# Central_march16.net
KiCad netlist of a schematic drawn in EAGLE
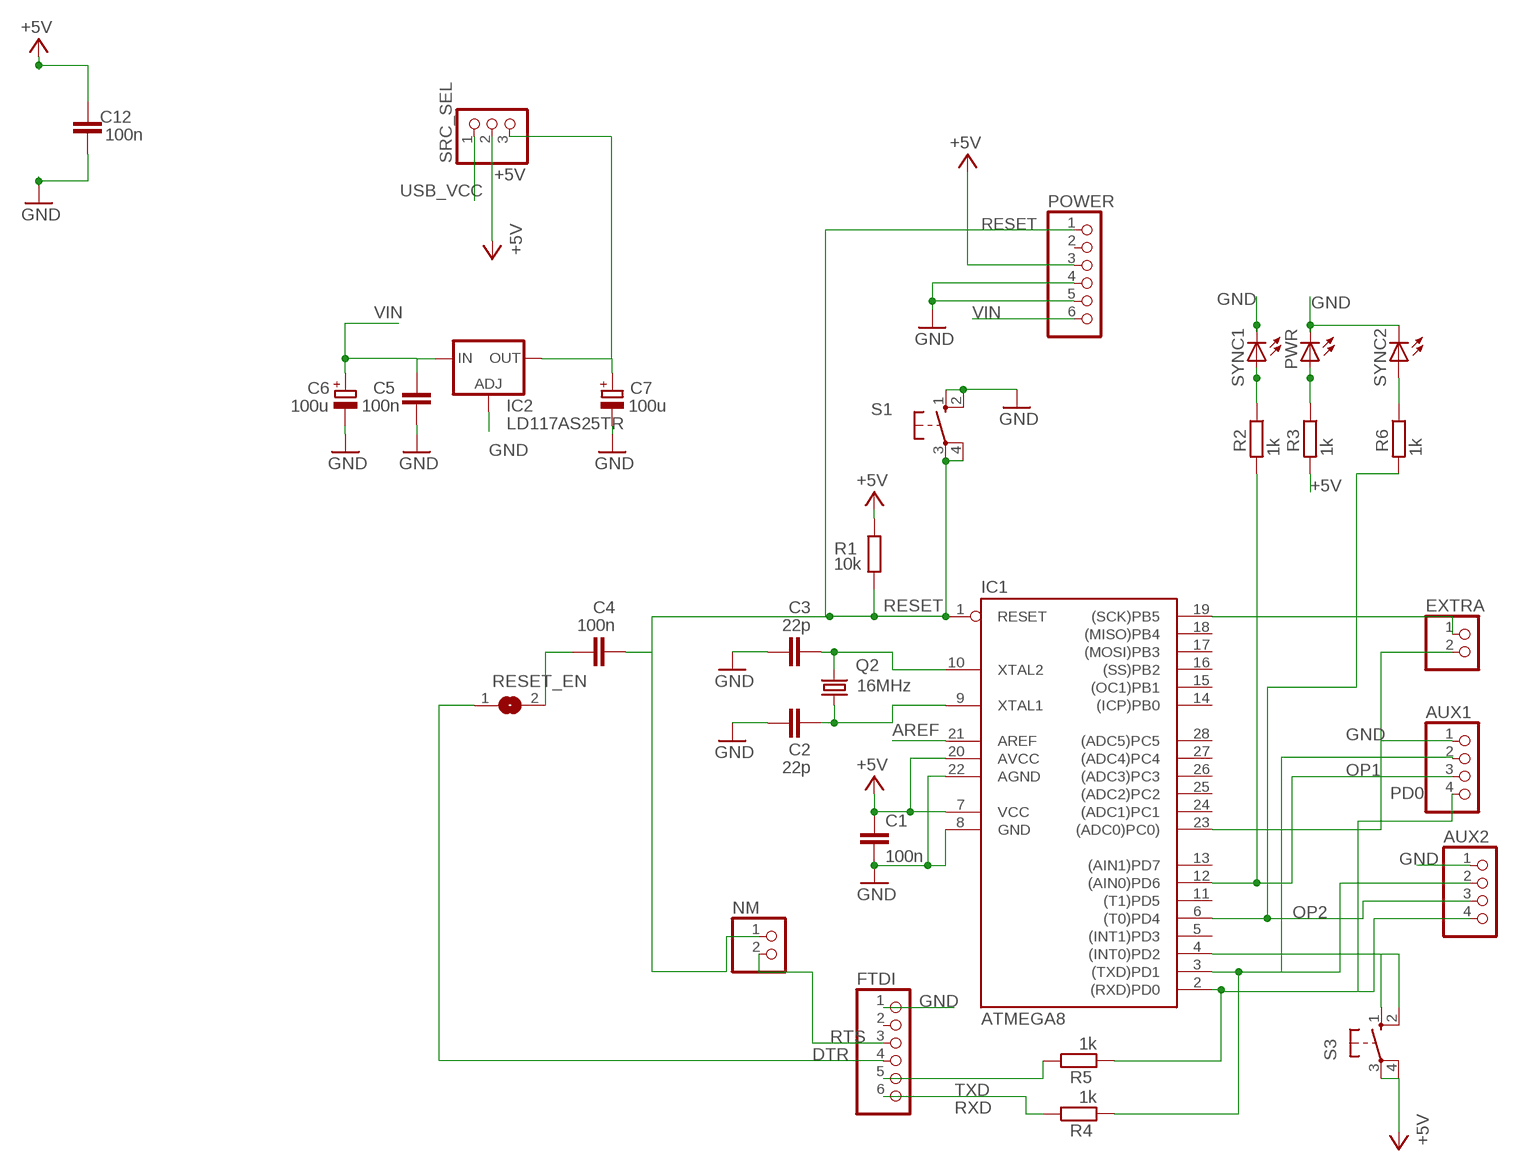
[diagram p0: schematic, sheet 1]

(export (version "E")
  (design (tool "Eeschema 10.0.6"))
  (components
    (comp (ref "AUX1")
      (value "PINHD-1X4")
      (footprint "eagle-import:1X04")
      (libsource (lib "eagle-import") (part "PINHD-1X4"))
    )
    (comp (ref "AUX2")
      (value "PINHD-1X4")
      (footprint "eagle-import:1X04")
      (libsource (lib "eagle-import") (part "PINHD-1X4"))
    )
    (comp (ref "C1")
      (value "100n")
      (footprint "eagle-import:C1206")
      (libsource (lib "eagle-import") (part "C-EUC1206"))
    )
    (comp (ref "C2")
      (value "22p")
      (footprint "eagle-import:C1206")
      (libsource (lib "eagle-import") (part "C-EUC1206"))
    )
    (comp (ref "C3")
      (value "22p")
      (footprint "eagle-import:C1206")
      (libsource (lib "eagle-import") (part "C-EUC1206"))
    )
    (comp (ref "C4")
      (value "100n")
      (footprint "eagle-import:C1206")
      (libsource (lib "eagle-import") (part "C-EUC1206"))
    )
    (comp (ref "C5")
      (value "100n")
      (footprint "eagle-import:C1206")
      (libsource (lib "eagle-import") (part "C-EUC1206"))
    )
    (comp (ref "C6")
      (value "100u")
      (footprint "eagle-import:PANASONIC_D")
      (libsource (lib "eagle-import") (part "CPOL-EUD"))
    )
    (comp (ref "C7")
      (value "100u")
      (footprint "eagle-import:PANASONIC_D")
      (libsource (lib "eagle-import") (part "CPOL-EUD"))
    )
    (comp (ref "C12")
      (value "100n")
      (footprint "eagle-import:C1206")
      (libsource (lib "eagle-import") (part "C-EUC1206"))
    )
    (comp (ref "EXTRA")
      (value "PINHD-1X2")
      (footprint "eagle-import:1X02")
      (libsource (lib "eagle-import") (part "PINHD-1X2"))
    )
    (comp (ref "FTDI")
      (value "PINHD-1X6")
      (footprint "eagle-import:1X06")
      (libsource (lib "eagle-import") (part "PINHD-1X6"))
    )
    (comp (ref "IC1")
      (value "ATMEGA8")
      (footprint "eagle-import:DIL28-3")
      (libsource (lib "eagle-import") (part "AT90S4433P"))
    )
    (comp (ref "IC2")
      (value "LD117AS25TR")
      (footprint "eagle-import:SOT223")
      (libsource (lib "eagle-import") (part "LD117A?S25TR"))
    )
    (comp (ref "NM")
      (value "PINHD-1X2")
      (footprint "eagle-import:1X02")
      (libsource (lib "eagle-import") (part "PINHD-1X2"))
    )
    (comp (ref "POWER")
      (value "PINHD-1X6")
      (footprint "eagle-import:1X06")
      (libsource (lib "eagle-import") (part "PINHD-1X6"))
    )
    (comp (ref "PWR")
      (value "LEDCHIPLED_1206")
      (footprint "eagle-import:CHIPLED_1206")
      (libsource (lib "eagle-import") (part "LEDCHIPLED_1206"))
    )
    (comp (ref "Q2")
      (value "16MHz")
      (footprint "eagle-import:HC49_S")
      (libsource (lib "eagle-import") (part "CRYTALHC49S"))
    )
    (comp (ref "R1")
      (value "10k")
      (footprint "eagle-import:R1206")
      (libsource (lib "eagle-import") (part "R-EU_R1206"))
    )
    (comp (ref "R2")
      (value "1k")
      (footprint "eagle-import:R1206")
      (libsource (lib "eagle-import") (part "R-EU_R1206"))
    )
    (comp (ref "R3")
      (value "1k")
      (footprint "eagle-import:R1206")
      (libsource (lib "eagle-import") (part "R-EU_R1206"))
    )
    (comp (ref "R4")
      (value "1k")
      (footprint "eagle-import:R1206")
      (libsource (lib "eagle-import") (part "R-EU_R1206"))
    )
    (comp (ref "R5")
      (value "1k")
      (footprint "eagle-import:R1206")
      (libsource (lib "eagle-import") (part "R-EU_R1206"))
    )
    (comp (ref "R6")
      (value "1k")
      (footprint "eagle-import:R1206")
      (libsource (lib "eagle-import") (part "R-EU_R1206"))
    )
    (comp (ref "RESET_EN")
      (value "SJ")
      (footprint "eagle-import:SJ")
      (libsource (lib "eagle-import") (part "SJ"))
    )
    (comp (ref "S1")
      (value "10-XX")
      (footprint "eagle-import:B3F-10XX")
      (fields (field (name "MPN") "B3F-1000"))
      (libsource (lib "eagle-import") (part "10-XX"))
    )
    (comp (ref "S3")
      (value "10-XX")
      (footprint "eagle-import:B3F-10XX")
      (fields (field (name "MPN") "B3F-1000"))
      (libsource (lib "eagle-import") (part "10-XX"))
    )
    (comp (ref "SRC_SEL")
      (value "PINHD-1X3")
      (footprint "eagle-import:1X03")
      (libsource (lib "eagle-import") (part "PINHD-1X3"))
    )
    (comp (ref "SYNC1")
      (value "LEDCHIPLED_1206")
      (footprint "eagle-import:CHIPLED_1206")
      (libsource (lib "eagle-import") (part "LEDCHIPLED_1206"))
    )
    (comp (ref "SYNC2")
      (value "LEDCHIPLED_1206")
      (footprint "eagle-import:CHIPLED_1206")
      (libsource (lib "eagle-import") (part "LEDCHIPLED_1206"))
    )
  )
  (nets
    (net (code "1") (name "+5V") (class "Default")
      (node (ref "C1") (pin "1") (pinfunction "1_1") (pintype "passive"))
      (node (ref "C12") (pin "2") (pinfunction "2_2") (pintype "passive"))
      (node (ref "IC1") (pin "20") (pinfunction "AVCC_20") (pintype "power_in"))
      (node (ref "IC1") (pin "7") (pinfunction "VCC_7") (pintype "power_in"))
      (node (ref "POWER") (pin "3") (pinfunction "3_3") (pintype "passive"))
      (node (ref "R1") (pin "2") (pinfunction "2_2") (pintype "passive"))
      (node (ref "R3") (pin "2") (pinfunction "2_2") (pintype "passive"))
      (node (ref "S3") (pin "3") (pinfunction "P_3") (pintype "passive"))
      (node (ref "S3") (pin "4") (pinfunction "P1_4") (pintype "passive"))
      (node (ref "SRC_SEL") (pin "2") (pinfunction "2_2") (pintype "passive"))
    )
    (net (code "2") (name "/AREF") (class "Default")
      (node (ref "IC1") (pin "21") (pinfunction "AREF_21") (pintype "power_in"))
    )
    (net (code "3") (name "/DTR") (class "Default")
      (node (ref "FTDI") (pin "4") (pinfunction "4_4") (pintype "passive"))
      (node (ref "RESET_EN") (pin "1") (pinfunction "1_1") (pintype "passive"))
    )
    (net (code "4") (name "/OP1") (class "Default")
      (node (ref "AUX1") (pin "3") (pinfunction "3_3") (pintype "passive"))
      (node (ref "IC1") (pin "12") (pinfunction "(AIN0)PD6_12") (pintype "bidirectional"))
      (node (ref "R2") (pin "2") (pinfunction "2_2") (pintype "passive"))
    )
    (net (code "5") (name "/OP2") (class "Default")
      (node (ref "AUX2") (pin "3") (pinfunction "3_3") (pintype "passive"))
      (node (ref "IC1") (pin "6") (pinfunction "(T0)PD4_6") (pintype "bidirectional"))
      (node (ref "R6") (pin "2") (pinfunction "2_2") (pintype "passive"))
    )
    (net (code "6") (name "/PD0") (class "Default")
      (node (ref "AUX1") (pin "4") (pinfunction "4_4") (pintype "passive"))
      (node (ref "AUX2") (pin "4") (pinfunction "4_4") (pintype "passive"))
      (node (ref "IC1") (pin "2") (pinfunction "(RXD)PD0_2") (pintype "bidirectional"))
      (node (ref "R5") (pin "2") (pinfunction "2_2") (pintype "passive"))
    )
    (net (code "7") (name "/RESET") (class "Default")
      (node (ref "C4") (pin "2") (pinfunction "2_2") (pintype "passive"))
      (node (ref "IC1") (pin "1") (pinfunction "RESET_1") (pintype "input"))
      (node (ref "NM") (pin "1") (pinfunction "1_1") (pintype "passive"))
      (node (ref "POWER") (pin "1") (pinfunction "1_1") (pintype "passive"))
      (node (ref "R1") (pin "1") (pinfunction "1_1") (pintype "passive"))
      (node (ref "S1") (pin "3") (pinfunction "P_3") (pintype "passive"))
      (node (ref "S1") (pin "4") (pinfunction "P1_4") (pintype "passive"))
    )
    (net (code "8") (name "/RTS") (class "Default")
      (node (ref "FTDI") (pin "3") (pinfunction "3_3") (pintype "passive"))
      (node (ref "NM") (pin "2") (pinfunction "2_2") (pintype "passive"))
    )
    (net (code "9") (name "/RXD") (class "Default")
      (node (ref "FTDI") (pin "6") (pinfunction "6_6") (pintype "passive"))
      (node (ref "R4") (pin "1") (pinfunction "1_1") (pintype "passive"))
    )
    (net (code "10") (name "/TXD") (class "Default")
      (node (ref "FTDI") (pin "5") (pinfunction "5_5") (pintype "passive"))
      (node (ref "R5") (pin "1") (pinfunction "1_1") (pintype "passive"))
    )
    (net (code "11") (name "/USB_VCC") (class "Default")
      (node (ref "SRC_SEL") (pin "1") (pinfunction "1_1") (pintype "passive"))
    )
    (net (code "12") (name "/VIN") (class "Default")
      (node (ref "C5") (pin "2") (pinfunction "2_2") (pintype "passive"))
      (node (ref "C6") (pin "+") (pinfunction "+_+") (pintype "passive"))
      (node (ref "IC2") (pin "3") (pinfunction "IN_3") (pintype "input"))
      (node (ref "POWER") (pin "6") (pinfunction "6_6") (pintype "passive"))
    )
    (net (code "13") (name "GND") (class "Default")
      (node (ref "AUX1") (pin "1") (pinfunction "1_1") (pintype "passive"))
      (node (ref "AUX2") (pin "1") (pinfunction "1_1") (pintype "passive"))
      (node (ref "C1") (pin "2") (pinfunction "2_2") (pintype "passive"))
      (node (ref "C12") (pin "1") (pinfunction "1_1") (pintype "passive"))
      (node (ref "C2") (pin "1") (pinfunction "1_1") (pintype "passive"))
      (node (ref "C3") (pin "1") (pinfunction "1_1") (pintype "passive"))
      (node (ref "C5") (pin "1") (pinfunction "1_1") (pintype "passive"))
      (node (ref "C6") (pin "-") (pinfunction "-_-") (pintype "passive"))
      (node (ref "C7") (pin "-") (pinfunction "-_-") (pintype "passive"))
      (node (ref "FTDI") (pin "1") (pinfunction "1_1") (pintype "passive"))
      (node (ref "IC1") (pin "22") (pinfunction "AGND_22") (pintype "power_in"))
      (node (ref "IC1") (pin "8") (pinfunction "GND_8") (pintype "power_in"))
      (node (ref "IC2") (pin "1") (pinfunction "ADJ_1") (pintype "input"))
      (node (ref "POWER") (pin "4") (pinfunction "4_4") (pintype "passive"))
      (node (ref "POWER") (pin "5") (pinfunction "5_5") (pintype "passive"))
      (node (ref "PWR") (pin "C") (pinfunction "C_C") (pintype "passive"))
      (node (ref "S1") (pin "1") (pinfunction "S_1") (pintype "passive"))
      (node (ref "S1") (pin "2") (pinfunction "S1_2") (pintype "passive"))
      (node (ref "SYNC1") (pin "C") (pinfunction "C_C") (pintype "passive"))
      (node (ref "SYNC2") (pin "C") (pinfunction "C_C") (pintype "passive"))
    )
    (net (code "14") (name "Net-(C4-Pad1)") (class "Default")
      (node (ref "C4") (pin "1") (pinfunction "1_1") (pintype "passive"))
      (node (ref "RESET_EN") (pin "2") (pinfunction "2_2") (pintype "passive"))
    )
    (net (code "15") (name "Net-(IC1-(ADC0)PC0))") (class "Default")
      (node (ref "EXTRA") (pin "2") (pinfunction "2_2") (pintype "passive"))
      (node (ref "IC1") (pin "23") (pinfunction "(ADC0)PC0)_23") (pintype "bidirectional"))
    )
    (net (code "16") (name "Net-(IC1-(INT0)PD2)") (class "Default")
      (node (ref "IC1") (pin "4") (pinfunction "(INT0)PD2_4") (pintype "bidirectional"))
      (node (ref "S3") (pin "1") (pinfunction "S_1") (pintype "passive"))
      (node (ref "S3") (pin "2") (pinfunction "S1_2") (pintype "passive"))
    )
    (net (code "17") (name "Net-(IC1-(SCK)PB5)") (class "Default")
      (node (ref "EXTRA") (pin "1") (pinfunction "1_1") (pintype "passive"))
      (node (ref "IC1") (pin "19") (pinfunction "(SCK)PB5_19") (pintype "bidirectional"))
    )
    (net (code "18") (name "Net-(IC1-(TXD)PD1)") (class "Default")
      (node (ref "AUX1") (pin "2") (pinfunction "2_2") (pintype "passive"))
      (node (ref "AUX2") (pin "2") (pinfunction "2_2") (pintype "passive"))
      (node (ref "IC1") (pin "3") (pinfunction "(TXD)PD1_3") (pintype "bidirectional"))
      (node (ref "R4") (pin "2") (pinfunction "2_2") (pintype "passive"))
    )
    (net (code "19") (name "Net-(IC1-XTAL1)") (class "Default")
      (node (ref "C2") (pin "2") (pinfunction "2_2") (pintype "passive"))
      (node (ref "IC1") (pin "9") (pinfunction "XTAL1_9") (pintype "bidirectional"))
      (node (ref "Q2") (pin "1") (pinfunction "1_1") (pintype "passive"))
    )
    (net (code "20") (name "Net-(IC1-XTAL2)") (class "Default")
      (node (ref "C3") (pin "2") (pinfunction "2_2") (pintype "passive"))
      (node (ref "IC1") (pin "10") (pinfunction "XTAL2_10") (pintype "bidirectional"))
      (node (ref "Q2") (pin "2") (pinfunction "2_2") (pintype "passive"))
    )
    (net (code "21") (name "Net-(IC2-OUT)") (class "Default")
      (node (ref "C7") (pin "+") (pinfunction "+_+") (pintype "passive"))
      (node (ref "IC2") (pin "4") (pinfunction "OUT_4") (pintype "passive"))
      (node (ref "SRC_SEL") (pin "3") (pinfunction "3_3") (pintype "passive"))
    )
    (net (code "22") (name "Net-(PWR-PadA)") (class "Default")
      (node (ref "PWR") (pin "A") (pinfunction "A_A") (pintype "passive"))
      (node (ref "R3") (pin "1") (pinfunction "1_1") (pintype "passive"))
    )
    (net (code "23") (name "Net-(R2-Pad1)") (class "Default")
      (node (ref "R2") (pin "1") (pinfunction "1_1") (pintype "passive"))
      (node (ref "SYNC1") (pin "A") (pinfunction "A_A") (pintype "passive"))
    )
    (net (code "24") (name "Net-(R6-Pad1)") (class "Default")
      (node (ref "R6") (pin "1") (pinfunction "1_1") (pintype "passive"))
      (node (ref "SYNC2") (pin "A") (pinfunction "A_A") (pintype "passive"))
    )
    (net (code "25") (name "unconnected-(FTDI-Pad2)") (class "Default")
      (node (ref "FTDI") (pin "2") (pinfunction "2_2") (pintype "passive"))
    )
    (net (code "26") (name "unconnected-(IC1-(ADC1)PC1-Pad24)") (class "Default")
      (node (ref "IC1") (pin "24") (pinfunction "(ADC1)PC1_24") (pintype "bidirectional"))
    )
    (net (code "27") (name "unconnected-(IC1-(ADC2)PC2-Pad25)") (class "Default")
      (node (ref "IC1") (pin "25") (pinfunction "(ADC2)PC2_25") (pintype "bidirectional"))
    )
    (net (code "28") (name "unconnected-(IC1-(ADC3)PC3-Pad26)") (class "Default")
      (node (ref "IC1") (pin "26") (pinfunction "(ADC3)PC3_26") (pintype "bidirectional"))
    )
    (net (code "29") (name "unconnected-(IC1-(ADC4)PC4-Pad27)") (class "Default")
      (node (ref "IC1") (pin "27") (pinfunction "(ADC4)PC4_27") (pintype "bidirectional"))
    )
    (net (code "30") (name "unconnected-(IC1-(ADC5)PC5-Pad28)") (class "Default")
      (node (ref "IC1") (pin "28") (pinfunction "(ADC5)PC5_28") (pintype "bidirectional"))
    )
    (net (code "31") (name "unconnected-(IC1-(AIN1)PD7-Pad13)") (class "Default")
      (node (ref "IC1") (pin "13") (pinfunction "(AIN1)PD7_13") (pintype "bidirectional"))
    )
    (net (code "32") (name "unconnected-(IC1-(ICP)PB0-Pad14)") (class "Default")
      (node (ref "IC1") (pin "14") (pinfunction "(ICP)PB0_14") (pintype "bidirectional"))
    )
    (net (code "33") (name "unconnected-(IC1-(INT1)PD3-Pad5)") (class "Default")
      (node (ref "IC1") (pin "5") (pinfunction "(INT1)PD3_5") (pintype "bidirectional"))
    )
    (net (code "34") (name "unconnected-(IC1-(MISO)PB4-Pad18)") (class "Default")
      (node (ref "IC1") (pin "18") (pinfunction "(MISO)PB4_18") (pintype "bidirectional"))
    )
    (net (code "35") (name "unconnected-(IC1-(MOSI)PB3-Pad17)") (class "Default")
      (node (ref "IC1") (pin "17") (pinfunction "(MOSI)PB3_17") (pintype "bidirectional"))
    )
    (net (code "36") (name "unconnected-(IC1-(OC1)PB1-Pad15)") (class "Default")
      (node (ref "IC1") (pin "15") (pinfunction "(OC1)PB1_15") (pintype "bidirectional"))
    )
    (net (code "37") (name "unconnected-(IC1-(SS)PB2-Pad16)") (class "Default")
      (node (ref "IC1") (pin "16") (pinfunction "(SS)PB2_16") (pintype "bidirectional"))
    )
    (net (code "38") (name "unconnected-(IC1-(T1)PD5-Pad11)") (class "Default")
      (node (ref "IC1") (pin "11") (pinfunction "(T1)PD5_11") (pintype "bidirectional"))
    )
    (net (code "39") (name "unconnected-(POWER-Pad2)") (class "Default")
      (node (ref "POWER") (pin "2") (pinfunction "2_2") (pintype "passive"))
    )
  )
)
